# Lamp_Logic_Board_3.net
KiCad netlist of a schematic drawn in EAGLE
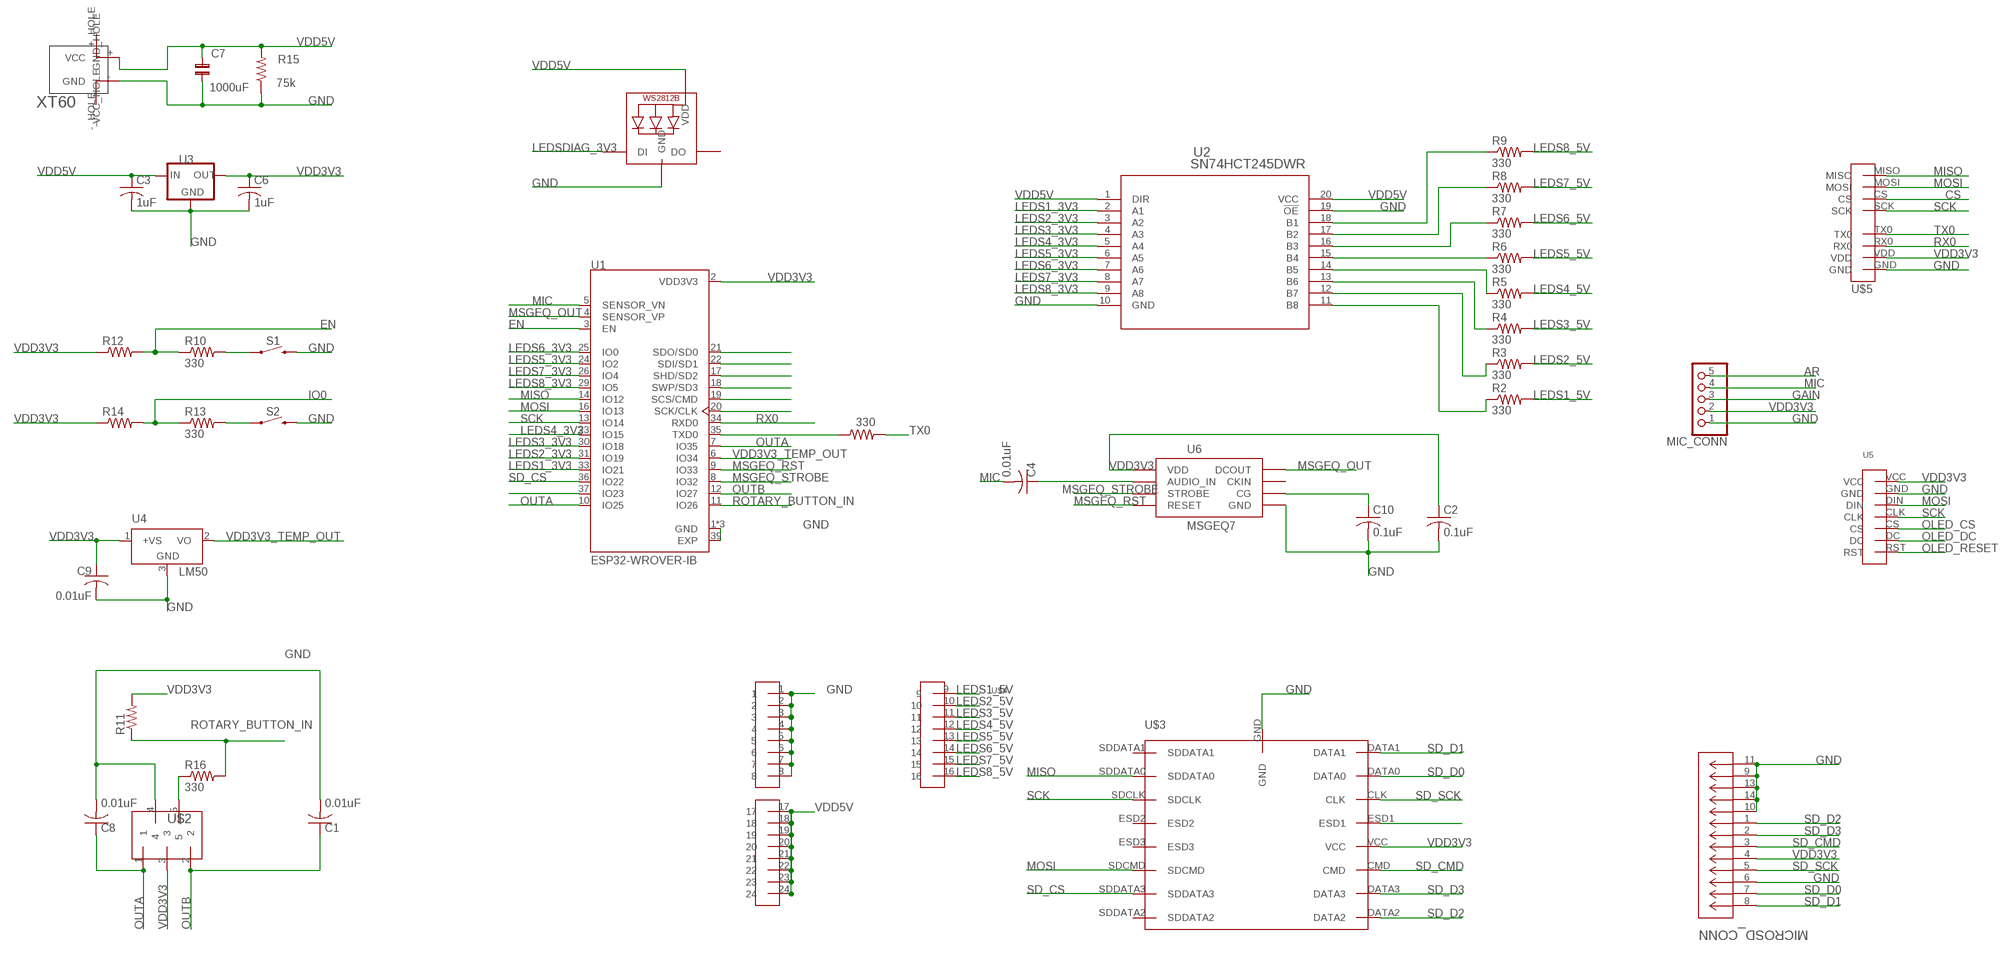
[diagram p0: schematic, sheet 1]

(export (version "E")
  (design (tool "Eeschema 10.0.6"))
  (components
    (comp (ref "C1")
      (value "0.01uF")
      (footprint "eagle-import:C0402")
      (libsource (lib "eagle-import") (part "C-USC0402"))
    )
    (comp (ref "C2")
      (value "0.1uF")
      (footprint "eagle-import:C0805")
      (libsource (lib "eagle-import") (part "C-USC0805"))
    )
    (comp (ref "C3")
      (value "1uF")
      (footprint "eagle-import:C0402")
      (libsource (lib "eagle-import") (part "C-USC0402"))
    )
    (comp (ref "C4")
      (value "0.01uF")
      (footprint "eagle-import:C0402")
      (libsource (lib "eagle-import") (part "C-USC0402"))
    )
    (comp (ref "C6")
      (value "1uF")
      (footprint "eagle-import:C0402")
      (libsource (lib "eagle-import") (part "C-USC0402"))
    )
    (comp (ref "C7")
      (value "1000uF")
      (footprint "eagle-import:ENP2,0-5")
      (libsource (lib "eagle-import") (part "C-BP-2,0X5"))
    )
    (comp (ref "C8")
      (value "0.01uF")
      (footprint "eagle-import:C0402")
      (libsource (lib "eagle-import") (part "C-USC0402"))
    )
    (comp (ref "C9")
      (value "0.01uF")
      (footprint "eagle-import:C0402")
      (libsource (lib "eagle-import") (part "C-USC0402"))
    )
    (comp (ref "C10")
      (value "0.1uF")
      (footprint "eagle-import:C0805")
      (libsource (lib "eagle-import") (part "C-USC0805"))
    )
    (comp (ref "LED1")
      (value "WS2812B5050")
      (footprint "eagle-import:WS2812B")
      (fields (field (name "MF") "Seeed Technology") (field (name "MP") "WS2812B"))
      (libsource (lib "eagle-import") (part "WS2812B5050"))
    )
    (comp (ref "MICROSD_CONN")
      (value "LLC")
      (footprint "eagle-import:CON00218_8")
      (libsource (lib "eagle-import") (part "LLC"))
    )
    (comp (ref "MIC_CONN")
      (value "PINHD-1X5")
      (footprint "eagle-import:1X05")
      (libsource (lib "eagle-import") (part "PINHD-1X5"))
    )
    (comp (ref "R1")
      (value "330")
      (footprint "eagle-import:R1206")
      (libsource (lib "eagle-import") (part "R-US_R1206"))
    )
    (comp (ref "R2")
      (value "330")
      (footprint "eagle-import:R1206")
      (libsource (lib "eagle-import") (part "R-US_R1206"))
    )
    (comp (ref "R3")
      (value "330")
      (footprint "eagle-import:R1206")
      (libsource (lib "eagle-import") (part "R-US_R1206"))
    )
    (comp (ref "R4")
      (value "330")
      (footprint "eagle-import:R1206")
      (libsource (lib "eagle-import") (part "R-US_R1206"))
    )
    (comp (ref "R5")
      (value "330")
      (footprint "eagle-import:R1206")
      (libsource (lib "eagle-import") (part "R-US_R1206"))
    )
    (comp (ref "R6")
      (value "330")
      (footprint "eagle-import:R1206")
      (libsource (lib "eagle-import") (part "R-US_R1206"))
    )
    (comp (ref "R7")
      (value "330")
      (footprint "eagle-import:R1206")
      (libsource (lib "eagle-import") (part "R-US_R1206"))
    )
    (comp (ref "R8")
      (value "330")
      (footprint "eagle-import:R1206")
      (libsource (lib "eagle-import") (part "R-US_R1206"))
    )
    (comp (ref "R9")
      (value "330")
      (footprint "eagle-import:R1206")
      (libsource (lib "eagle-import") (part "R-US_R1206"))
    )
    (comp (ref "R10")
      (value "330")
      (footprint "eagle-import:R1206")
      (libsource (lib "eagle-import") (part "R-US_R1206"))
    )
    (comp (ref "R11")
      (value "R-US_R0603")
      (footprint "eagle-import:R0603")
      (libsource (lib "eagle-import") (part "R-US_R0603"))
    )
    (comp (ref "R12")
      (value "R-US_R0603")
      (footprint "eagle-import:R0603")
      (libsource (lib "eagle-import") (part "R-US_R0603"))
    )
    (comp (ref "R13")
      (value "330")
      (footprint "eagle-import:R1206")
      (libsource (lib "eagle-import") (part "R-US_R1206"))
    )
    (comp (ref "R14")
      (value "R-US_R0603")
      (footprint "eagle-import:R0603")
      (libsource (lib "eagle-import") (part "R-US_R0603"))
    )
    (comp (ref "R15")
      (value "75k")
      (footprint "eagle-import:0309_12")
      (libsource (lib "eagle-import") (part "R-US_0309/12"))
    )
    (comp (ref "R16")
      (value "330")
      (footprint "eagle-import:R1206")
      (libsource (lib "eagle-import") (part "R-US_R1206"))
    )
    (comp (ref "S1")
      (value "MOMENTARY-SWITCH-SPST-SMD-6.0X3.5MM")
      (footprint "eagle-import:TACTILE_SWITCH_SMD_6.0X3.5MM")
      (libsource (lib "eagle-import") (part "MOMENTARY-SWITCH-SPST-SMD-6.0X3.5MM"))
    )
    (comp (ref "S2")
      (value "MOMENTARY-SWITCH-SPST-SMD-6.0X3.5MM")
      (footprint "eagle-import:TACTILE_SWITCH_SMD_6.0X3.5MM")
      (libsource (lib "eagle-import") (part "MOMENTARY-SWITCH-SPST-SMD-6.0X3.5MM"))
    )
    (comp (ref "U$1")
      (value "XT60")
      (footprint "eagle-import:XT60")
      (libsource (lib "eagle-import") (part "XT60"))
    )
    (comp (ref "U$2")
      (value "EN11-HSM1AF15")
      (footprint "eagle-import:EN11-HSM")
      (libsource (lib "eagle-import") (part "EN11-HSM1AF15"))
    )
    (comp (ref "U$3")
      (value "CM1624-08DE")
      (footprint "eagle-import:CM1624-08DE")
      (libsource (lib "eagle-import") (part "CM1624-08DE"))
    )
    (comp (ref "U$4")
      (value "3X8PINHEAD")
      (footprint "eagle-import:3X8PINHEAD")
      (libsource (lib "eagle-import") (part "3X8PINHEAD"))
    )
    (comp (ref "U$5")
      (value "2X4PINHEAD")
      (footprint "eagle-import:2X4PINHEAD")
      (libsource (lib "eagle-import") (part "2X4PINHEAD"))
    )
    (comp (ref "U1")
      (value "ESP32-WROVER-IB")
      (footprint "eagle-import:XCVR_ESP32-WROVER-I")
      (fields (field (name "MF") "Espressif Systems") (field (name "MP") "ESP32-WROVER-I"))
      (libsource (lib "eagle-import") (part "ESP32-WROVER-I"))
    )
    (comp (ref "U2")
      (value "SN74HCT245DWR")
      (footprint "eagle-import:DW20")
      (libsource (lib "eagle-import") (part "SN74HCT245DWR"))
    )
    (comp (ref "U3")
      (value "LM1117MP-1.8")
      (footprint "eagle-import:SOT223")
      (fields (field (name "MF") "Texas Instruments"))
      (libsource (lib "eagle-import") (part "LM1117?-MP1.8"))
    )
    (comp (ref "U4")
      (value "LM50")
      (footprint "eagle-import:SOT23")
      (libsource (lib "eagle-import") (part "LM50"))
    )
    (comp (ref "U5")
      (value "SPIOLED_STANDOFF")
      (footprint "eagle-import:SPIOLED_STADOFF")
      (libsource (lib "eagle-import") (part "SPIOLED_STANDOFF"))
    )
    (comp (ref "U6")
      (value "MSGEQ7DIL")
      (footprint "eagle-import:DIL-08")
      (fields
        (field (name "DIGI-KEY_PART_NUMBER") "1568-1544-ND")
        (field (name "MF") "SparkFun Electronics")
        (field (name "MP") "MSGEQ7")
      )
      (libsource (lib "eagle-import") (part "MSGEQ7DIL"))
    )
  )
  (nets
    (net (code "1") (name "/AR") (class "Default")
      (node (ref "MIC_CONN") (pin "5") (pinfunction "5_5") (pintype "passive"))
    )
    (net (code "2") (name "/CS") (class "Default")
      (node (ref "U$5") (pin "CS") (pinfunction "CS_CS") (pintype "bidirectional"))
    )
    (net (code "3") (name "/EN") (class "Default")
      (node (ref "R10") (pin "1") (pinfunction "1_1") (pintype "passive"))
      (node (ref "R12") (pin "2") (pinfunction "2_2") (pintype "passive"))
      (node (ref "U1") (pin "3") (pinfunction "EN_3") (pintype "input"))
    )
    (net (code "4") (name "/GAIN") (class "Default")
      (node (ref "MIC_CONN") (pin "3") (pinfunction "3_3") (pintype "passive"))
    )
    (net (code "5") (name "/GND") (class "Default")
      (node (ref "C1") (pin "2") (pinfunction "2_2") (pintype "passive"))
      (node (ref "C10") (pin "2") (pinfunction "2_2") (pintype "passive"))
      (node (ref "C2") (pin "2") (pinfunction "2_2") (pintype "passive"))
      (node (ref "C3") (pin "2") (pinfunction "2_2") (pintype "passive"))
      (node (ref "C6") (pin "2") (pinfunction "2_2") (pintype "passive"))
      (node (ref "C7") (pin "1") (pinfunction "1_1") (pintype "passive"))
      (node (ref "C8") (pin "2") (pinfunction "2_2") (pintype "passive"))
      (node (ref "C9") (pin "2") (pinfunction "2_2") (pintype "passive"))
      (node (ref "LED1") (pin "3-GND") (pinfunction "GND_3-GND") (pintype "power_in"))
      (node (ref "MICROSD_CONN") (pin "10") (pinfunction "10_10") (pintype "passive"))
      (node (ref "MICROSD_CONN") (pin "11") (pinfunction "11_11") (pintype "passive"))
      (node (ref "MICROSD_CONN") (pin "13") (pinfunction "13_13") (pintype "passive"))
      (node (ref "MICROSD_CONN") (pin "14") (pinfunction "14_14") (pintype "passive"))
      (node (ref "MICROSD_CONN") (pin "6") (pinfunction "6_6") (pintype "passive"))
      (node (ref "MICROSD_CONN") (pin "9") (pinfunction "9_9") (pintype "passive"))
      (node (ref "MIC_CONN") (pin "1") (pinfunction "1_1") (pintype "passive"))
      (node (ref "R15") (pin "1") (pinfunction "1_1") (pintype "passive"))
      (node (ref "S1") (pin "2") (pinfunction "2_2") (pintype "passive"))
      (node (ref "S2") (pin "2") (pinfunction "2_2") (pintype "passive"))
      (node (ref "U$1") (pin "-") (pinfunction "GND_-") (pintype "bidirectional"))
      (node (ref "U$2") (pin "4") (pinfunction "4_4") (pintype "bidirectional"))
      (node (ref "U$3") (pin "GND") (pinfunction "GND_GND") (pintype "bidirectional"))
      (node (ref "U$4") (pin "1") (pinfunction "1_1") (pintype "bidirectional"))
      (node (ref "U$4") (pin "2") (pinfunction "2_2") (pintype "bidirectional"))
      (node (ref "U$4") (pin "3") (pinfunction "3_3") (pintype "bidirectional"))
      (node (ref "U$4") (pin "4") (pinfunction "4_4") (pintype "bidirectional"))
      (node (ref "U$4") (pin "5") (pinfunction "5_5") (pintype "bidirectional"))
      (node (ref "U$4") (pin "6") (pinfunction "6_6") (pintype "bidirectional"))
      (node (ref "U$4") (pin "7") (pinfunction "7_7") (pintype "bidirectional"))
      (node (ref "U$4") (pin "8") (pinfunction "8_8") (pintype "bidirectional"))
      (node (ref "U$5") (pin "GND") (pinfunction "GND_GND") (pintype "bidirectional"))
      (node (ref "U1") (pin "1") (pinfunction "GND_1") (pintype "power_in"))
      (node (ref "U1") (pin "15") (pinfunction "GND_15") (pintype "power_in"))
      (node (ref "U1") (pin "38") (pinfunction "GND_38") (pintype "power_in"))
      (node (ref "U1") (pin "39") (pinfunction "EXP_39") (pintype "power_in"))
      (node (ref "U2") (pin "10") (pinfunction "GND_10") (pintype "power_in"))
      (node (ref "U2") (pin "19") (pinfunction "~{OE}_19") (pintype "input"))
      (node (ref "U3") (pin "1") (pinfunction "GND_1") (pintype "input"))
      (node (ref "U4") (pin "3") (pinfunction "GND_3") (pintype "power_in"))
      (node (ref "U5") (pin "GND") (pinfunction "GND_GND") (pintype "bidirectional"))
      (node (ref "U6") (pin "2") (pinfunction "GND_2") (pintype "bidirectional"))
    )
    (net (code "6") (name "/IO0") (class "Default")
      (node (ref "R13") (pin "1") (pinfunction "1_1") (pintype "passive"))
      (node (ref "R14") (pin "2") (pinfunction "2_2") (pintype "passive"))
    )
    (net (code "7") (name "/LEDS1_3V3") (class "Default")
      (node (ref "U1") (pin "33") (pinfunction "IO21_33") (pintype "bidirectional"))
      (node (ref "U2") (pin "2") (pinfunction "A1_2") (pintype "bidirectional"))
    )
    (net (code "8") (name "/LEDS1_5V") (class "Default")
      (node (ref "R2") (pin "2") (pinfunction "2_2") (pintype "passive"))
      (node (ref "U$4") (pin "9") (pinfunction "9_9") (pintype "bidirectional"))
    )
    (net (code "9") (name "/LEDS2_3V3") (class "Default")
      (node (ref "U1") (pin "31") (pinfunction "IO19_31") (pintype "bidirectional"))
      (node (ref "U2") (pin "3") (pinfunction "A2_3") (pintype "bidirectional"))
    )
    (net (code "10") (name "/LEDS2_5V") (class "Default")
      (node (ref "R3") (pin "2") (pinfunction "2_2") (pintype "passive"))
      (node (ref "U$4") (pin "10") (pinfunction "10_10") (pintype "bidirectional"))
    )
    (net (code "11") (name "/LEDS3_3V3") (class "Default")
      (node (ref "U1") (pin "30") (pinfunction "IO18_30") (pintype "bidirectional"))
      (node (ref "U2") (pin "4") (pinfunction "A3_4") (pintype "bidirectional"))
    )
    (net (code "12") (name "/LEDS3_5V") (class "Default")
      (node (ref "R4") (pin "2") (pinfunction "2_2") (pintype "passive"))
      (node (ref "U$4") (pin "11") (pinfunction "11_11") (pintype "bidirectional"))
    )
    (net (code "13") (name "/LEDS4_3V3") (class "Default")
      (node (ref "U1") (pin "23") (pinfunction "IO15_23") (pintype "bidirectional"))
      (node (ref "U2") (pin "5") (pinfunction "A4_5") (pintype "bidirectional"))
    )
    (net (code "14") (name "/LEDS4_5V") (class "Default")
      (node (ref "R5") (pin "2") (pinfunction "2_2") (pintype "passive"))
      (node (ref "U$4") (pin "12") (pinfunction "12_12") (pintype "bidirectional"))
    )
    (net (code "15") (name "/LEDS5_3V3") (class "Default")
      (node (ref "U1") (pin "24") (pinfunction "IO2_24") (pintype "bidirectional"))
      (node (ref "U2") (pin "6") (pinfunction "A5_6") (pintype "bidirectional"))
    )
    (net (code "16") (name "/LEDS5_5V") (class "Default")
      (node (ref "R6") (pin "2") (pinfunction "2_2") (pintype "passive"))
      (node (ref "U$4") (pin "13") (pinfunction "13_13") (pintype "bidirectional"))
    )
    (net (code "17") (name "/LEDS6_3V3") (class "Default")
      (node (ref "U1") (pin "25") (pinfunction "IO0_25") (pintype "bidirectional"))
      (node (ref "U2") (pin "7") (pinfunction "A6_7") (pintype "bidirectional"))
    )
    (net (code "18") (name "/LEDS6_5V") (class "Default")
      (node (ref "R7") (pin "2") (pinfunction "2_2") (pintype "passive"))
      (node (ref "U$4") (pin "14") (pinfunction "14_14") (pintype "bidirectional"))
    )
    (net (code "19") (name "/LEDS7_3V3") (class "Default")
      (node (ref "U1") (pin "26") (pinfunction "IO4_26") (pintype "bidirectional"))
      (node (ref "U2") (pin "8") (pinfunction "A7_8") (pintype "bidirectional"))
    )
    (net (code "20") (name "/LEDS7_5V") (class "Default")
      (node (ref "R8") (pin "2") (pinfunction "2_2") (pintype "passive"))
      (node (ref "U$4") (pin "15") (pinfunction "15_15") (pintype "bidirectional"))
    )
    (net (code "21") (name "/LEDS8_3V3") (class "Default")
      (node (ref "U1") (pin "29") (pinfunction "IO5_29") (pintype "bidirectional"))
      (node (ref "U2") (pin "9") (pinfunction "A8_9") (pintype "bidirectional"))
    )
    (net (code "22") (name "/LEDS8_5V") (class "Default")
      (node (ref "R9") (pin "2") (pinfunction "2_2") (pintype "passive"))
      (node (ref "U$4") (pin "16") (pinfunction "16_16") (pintype "bidirectional"))
    )
    (net (code "23") (name "/LEDSDIAG_3V3") (class "Default")
      (node (ref "LED1") (pin "4-DIN") (pinfunction "DI_4-DIN") (pintype "input"))
    )
    (net (code "24") (name "/MIC") (class "Default")
      (node (ref "C4") (pin "2") (pinfunction "2_2") (pintype "passive"))
      (node (ref "MIC_CONN") (pin "4") (pinfunction "4_4") (pintype "passive"))
      (node (ref "U1") (pin "5") (pinfunction "SENSOR_VN_5") (pintype "input"))
    )
    (net (code "25") (name "/MISO") (class "Default")
      (node (ref "U$3") (pin "SDDATA0") (pinfunction "SDDATA0_SDDATA0") (pintype "bidirectional"))
      (node (ref "U$5") (pin "MISO") (pinfunction "MISO_MISO") (pintype "bidirectional"))
      (node (ref "U1") (pin "14") (pinfunction "IO12_14") (pintype "bidirectional"))
    )
    (net (code "26") (name "/MOSI") (class "Default")
      (node (ref "U$3") (pin "SDCMD") (pinfunction "SDCMD_SDCMD") (pintype "bidirectional"))
      (node (ref "U$5") (pin "MOSI") (pinfunction "MOSI_MOSI") (pintype "bidirectional"))
      (node (ref "U1") (pin "16") (pinfunction "IO13_16") (pintype "bidirectional"))
      (node (ref "U5") (pin "DIN") (pinfunction "DIN_DIN") (pintype "bidirectional"))
    )
    (net (code "27") (name "/MSGEQ_OUT") (class "Default")
      (node (ref "U1") (pin "4") (pinfunction "SENSOR_VP_4") (pintype "input"))
      (node (ref "U6") (pin "3") (pinfunction "DCOUT_3") (pintype "bidirectional"))
    )
    (net (code "28") (name "/MSGEQ_RST") (class "Default")
      (node (ref "U1") (pin "9") (pinfunction "IO33_9") (pintype "bidirectional"))
      (node (ref "U6") (pin "7") (pinfunction "RESET_7") (pintype "input"))
    )
    (net (code "29") (name "/MSGEQ_STROBE") (class "Default")
      (node (ref "U1") (pin "8") (pinfunction "IO32_8") (pintype "bidirectional"))
      (node (ref "U6") (pin "4") (pinfunction "STROBE_4") (pintype "input"))
    )
    (net (code "30") (name "/OLED_CS") (class "Default")
      (node (ref "U5") (pin "CS") (pinfunction "CS_CS") (pintype "bidirectional"))
    )
    (net (code "31") (name "/OLED_DC") (class "Default")
      (node (ref "U5") (pin "DC") (pinfunction "DC_DC") (pintype "bidirectional"))
    )
    (net (code "32") (name "/OLED_RESET") (class "Default")
      (node (ref "U5") (pin "RST") (pinfunction "RST_RST") (pintype "bidirectional"))
    )
    (net (code "33") (name "/OUTA") (class "Default")
      (node (ref "C8") (pin "1") (pinfunction "1_1") (pintype "passive"))
      (node (ref "U$2") (pin "1") (pinfunction "1_1") (pintype "passive"))
      (node (ref "U1") (pin "10") (pinfunction "IO25_10") (pintype "bidirectional"))
      (node (ref "U1") (pin "7") (pinfunction "IO35_7") (pintype "input"))
    )
    (net (code "34") (name "/OUTB") (class "Default")
      (node (ref "C1") (pin "1") (pinfunction "1_1") (pintype "passive"))
      (node (ref "U$2") (pin "2") (pinfunction "2_2") (pintype "passive"))
      (node (ref "U1") (pin "12") (pinfunction "IO27_12") (pintype "bidirectional"))
    )
    (net (code "35") (name "/ROTARY_BUTTON_IN") (class "Default")
      (node (ref "R11") (pin "1") (pinfunction "1_1") (pintype "passive"))
      (node (ref "R16") (pin "2") (pinfunction "2_2") (pintype "passive"))
      (node (ref "U1") (pin "11") (pinfunction "IO26_11") (pintype "bidirectional"))
    )
    (net (code "36") (name "/RX0") (class "Default")
      (node (ref "U$5") (pin "RX0") (pinfunction "RX0_RX0") (pintype "bidirectional"))
      (node (ref "U1") (pin "34") (pinfunction "RXD0_34") (pintype "bidirectional"))
    )
    (net (code "37") (name "/SCK") (class "Default")
      (node (ref "U$3") (pin "SDCLK") (pinfunction "SDCLK_SDCLK") (pintype "bidirectional"))
      (node (ref "U$5") (pin "SCK") (pinfunction "SCK_SCK") (pintype "bidirectional"))
      (node (ref "U1") (pin "13") (pinfunction "IO14_13") (pintype "bidirectional"))
      (node (ref "U5") (pin "CLK") (pinfunction "CLK_CLK") (pintype "bidirectional"))
    )
    (net (code "38") (name "/SD_CMD") (class "Default")
      (node (ref "MICROSD_CONN") (pin "3") (pinfunction "3_3") (pintype "passive"))
      (node (ref "U$3") (pin "CMD") (pinfunction "CMD_CMD") (pintype "bidirectional"))
    )
    (net (code "39") (name "/SD_CS") (class "Default")
      (node (ref "U$3") (pin "SDDATA3") (pinfunction "SDDATA3_SDDATA3") (pintype "bidirectional"))
      (node (ref "U1") (pin "36") (pinfunction "IO22_36") (pintype "bidirectional"))
    )
    (net (code "40") (name "/SD_D0") (class "Default")
      (node (ref "MICROSD_CONN") (pin "7") (pinfunction "7_7") (pintype "passive"))
      (node (ref "U$3") (pin "DATA0") (pinfunction "DATA0_DATA0") (pintype "bidirectional"))
    )
    (net (code "41") (name "/SD_D1") (class "Default")
      (node (ref "MICROSD_CONN") (pin "8") (pinfunction "8_8") (pintype "passive"))
      (node (ref "U$3") (pin "DATA1") (pinfunction "DATA1_DATA1") (pintype "bidirectional"))
    )
    (net (code "42") (name "/SD_D2") (class "Default")
      (node (ref "MICROSD_CONN") (pin "1") (pinfunction "1_1") (pintype "passive"))
      (node (ref "U$3") (pin "DATA2") (pinfunction "DATA2_DATA2") (pintype "bidirectional"))
    )
    (net (code "43") (name "/SD_D3") (class "Default")
      (node (ref "MICROSD_CONN") (pin "2") (pinfunction "2_2") (pintype "passive"))
      (node (ref "U$3") (pin "DATA3") (pinfunction "DATA3_DATA3") (pintype "bidirectional"))
    )
    (net (code "44") (name "/SD_SCK") (class "Default")
      (node (ref "MICROSD_CONN") (pin "5") (pinfunction "5_5") (pintype "passive"))
      (node (ref "U$3") (pin "CLK") (pinfunction "CLK_CLK") (pintype "bidirectional"))
    )
    (net (code "45") (name "/TX0") (class "Default")
      (node (ref "R1") (pin "2") (pinfunction "2_2") (pintype "passive"))
      (node (ref "U$5") (pin "TX0") (pinfunction "TX0_TX0") (pintype "bidirectional"))
    )
    (net (code "46") (name "/VDD3V3") (class "Default")
      (node (ref "C2") (pin "1") (pinfunction "1_1") (pintype "passive"))
      (node (ref "C6") (pin "1") (pinfunction "1_1") (pintype "passive"))
      (node (ref "C9") (pin "1") (pinfunction "1_1") (pintype "passive"))
      (node (ref "MICROSD_CONN") (pin "4") (pinfunction "4_4") (pintype "passive"))
      (node (ref "MIC_CONN") (pin "2") (pinfunction "2_2") (pintype "passive"))
      (node (ref "R11") (pin "2") (pinfunction "2_2") (pintype "passive"))
      (node (ref "R12") (pin "1") (pinfunction "1_1") (pintype "passive"))
      (node (ref "R14") (pin "1") (pinfunction "1_1") (pintype "passive"))
      (node (ref "U$2") (pin "3") (pinfunction "3_3") (pintype "passive"))
      (node (ref "U$3") (pin "VCC") (pinfunction "VCC_VCC") (pintype "bidirectional"))
      (node (ref "U$5") (pin "VDD") (pinfunction "VDD_VDD") (pintype "bidirectional"))
      (node (ref "U1") (pin "2") (pinfunction "VDD3V3_2") (pintype "power_in"))
      (node (ref "U3") (pin "2") (pinfunction "OUT_2") (pintype "passive"))
      (node (ref "U3") (pin "4") (pinfunction "OUT_4") (pintype "passive"))
      (node (ref "U4") (pin "1") (pinfunction "+VS_1") (pintype "input"))
      (node (ref "U5") (pin "VCC") (pinfunction "VCC_VCC") (pintype "bidirectional"))
      (node (ref "U6") (pin "1") (pinfunction "VDD_1") (pintype "input"))
    )
    (net (code "47") (name "/VDD3V3_TEMP_OUT") (class "Default")
      (node (ref "U1") (pin "6") (pinfunction "IO34_6") (pintype "input"))
      (node (ref "U4") (pin "2") (pinfunction "VO_2") (pintype "input"))
    )
    (net (code "48") (name "/VDD5V") (class "Default")
      (node (ref "C3") (pin "1") (pinfunction "1_1") (pintype "passive"))
      (node (ref "C7") (pin "2") (pinfunction "2_2") (pintype "passive"))
      (node (ref "LED1") (pin "1-VDD") (pinfunction "VDD_1-VDD") (pintype "power_in"))
      (node (ref "R15") (pin "2") (pinfunction "2_2") (pintype "passive"))
      (node (ref "U$1") (pin "+") (pinfunction "VCC_+") (pintype "bidirectional"))
      (node (ref "U$4") (pin "17") (pinfunction "17_17") (pintype "bidirectional"))
      (node (ref "U$4") (pin "18") (pinfunction "18_18") (pintype "bidirectional"))
      (node (ref "U$4") (pin "19") (pinfunction "19_19") (pintype "bidirectional"))
      (node (ref "U$4") (pin "20") (pinfunction "20_20") (pintype "bidirectional"))
      (node (ref "U$4") (pin "21") (pinfunction "21_21") (pintype "bidirectional"))
      (node (ref "U$4") (pin "22") (pinfunction "22_22") (pintype "bidirectional"))
      (node (ref "U$4") (pin "23") (pinfunction "23_23") (pintype "bidirectional"))
      (node (ref "U$4") (pin "24") (pinfunction "24_24") (pintype "bidirectional"))
      (node (ref "U2") (pin "1") (pinfunction "DIR_1") (pintype "input"))
      (node (ref "U2") (pin "20") (pinfunction "VCC_20") (pintype "power_in"))
      (node (ref "U3") (pin "3") (pinfunction "IN_3") (pintype "input"))
    )
    (net (code "49") (name "Net-(R10-Pad2)") (class "Default")
      (node (ref "R10") (pin "2") (pinfunction "2_2") (pintype "passive"))
      (node (ref "S1") (pin "1") (pinfunction "1_1") (pintype "passive"))
    )
    (net (code "50") (name "Net-(R13-Pad2)") (class "Default")
      (node (ref "R13") (pin "2") (pinfunction "2_2") (pintype "passive"))
      (node (ref "S2") (pin "1") (pinfunction "1_1") (pintype "passive"))
    )
    (net (code "51") (name "Net-(R16-Pad1)") (class "Default")
      (node (ref "R16") (pin "1") (pinfunction "1_1") (pintype "passive"))
      (node (ref "U$2") (pin "5") (pinfunction "5_5") (pintype "bidirectional"))
    )
    (net (code "52") (name "Net-(U1-TXD0)") (class "Default")
      (node (ref "R1") (pin "1") (pinfunction "1_1") (pintype "passive"))
      (node (ref "U1") (pin "35") (pinfunction "TXD0_35") (pintype "bidirectional"))
    )
    (net (code "53") (name "Net-(U2-B1)") (class "Default")
      (node (ref "R9") (pin "1") (pinfunction "1_1") (pintype "passive"))
      (node (ref "U2") (pin "18") (pinfunction "B1_18") (pintype "bidirectional"))
    )
    (net (code "54") (name "Net-(U2-B2)") (class "Default")
      (node (ref "R8") (pin "1") (pinfunction "1_1") (pintype "passive"))
      (node (ref "U2") (pin "17") (pinfunction "B2_17") (pintype "bidirectional"))
    )
    (net (code "55") (name "Net-(U2-B3)") (class "Default")
      (node (ref "R7") (pin "1") (pinfunction "1_1") (pintype "passive"))
      (node (ref "U2") (pin "16") (pinfunction "B3_16") (pintype "bidirectional"))
    )
    (net (code "56") (name "Net-(U2-B4)") (class "Default")
      (node (ref "R6") (pin "1") (pinfunction "1_1") (pintype "passive"))
      (node (ref "U2") (pin "15") (pinfunction "B4_15") (pintype "bidirectional"))
    )
    (net (code "57") (name "Net-(U2-B5)") (class "Default")
      (node (ref "R5") (pin "1") (pinfunction "1_1") (pintype "passive"))
      (node (ref "U2") (pin "14") (pinfunction "B5_14") (pintype "bidirectional"))
    )
    (net (code "58") (name "Net-(U2-B6)") (class "Default")
      (node (ref "R4") (pin "1") (pinfunction "1_1") (pintype "passive"))
      (node (ref "U2") (pin "13") (pinfunction "B6_13") (pintype "bidirectional"))
    )
    (net (code "59") (name "Net-(U2-B7)") (class "Default")
      (node (ref "R3") (pin "1") (pinfunction "1_1") (pintype "passive"))
      (node (ref "U2") (pin "12") (pinfunction "B7_12") (pintype "bidirectional"))
    )
    (net (code "60") (name "Net-(U2-B8)") (class "Default")
      (node (ref "R2") (pin "1") (pinfunction "1_1") (pintype "passive"))
      (node (ref "U2") (pin "11") (pinfunction "B8_11") (pintype "bidirectional"))
    )
    (net (code "61") (name "Net-(U6-AUDIO_IN)") (class "Default")
      (node (ref "C4") (pin "1") (pinfunction "1_1") (pintype "passive"))
      (node (ref "U6") (pin "5") (pinfunction "AUDIO_IN_5") (pintype "input"))
    )
    (net (code "62") (name "Net-(U6-CG)") (class "Default")
      (node (ref "C10") (pin "1") (pinfunction "1_1") (pintype "passive"))
      (node (ref "U6") (pin "6") (pinfunction "CG_6") (pintype "bidirectional"))
    )
    (net (code "63") (name "unconnected-(LED1-DO-Pad2-DOUT)") (class "Default")
      (node (ref "LED1") (pin "2-DOUT") (pinfunction "DO_2-DOUT") (pintype "output"))
    )
    (net (code "64") (name "unconnected-(U$1-GND_HOLE-Pad-_HOLE)") (class "Default")
      (node (ref "U$1") (pin "-_HOLE") (pinfunction "GND_HOLE_-_HOLE") (pintype "bidirectional"))
    )
    (net (code "65") (name "unconnected-(U$1-VCC_HOLE-Pad+_HOLE)") (class "Default")
      (node (ref "U$1") (pin "+_HOLE") (pinfunction "VCC_HOLE_+_HOLE") (pintype "bidirectional"))
    )
    (net (code "66") (name "unconnected-(U$3-PadESD1)") (class "Default")
      (node (ref "U$3") (pin "ESD1") (pinfunction "ESD1_ESD1") (pintype "bidirectional"))
    )
    (net (code "67") (name "unconnected-(U$3-PadESD2)") (class "Default")
      (node (ref "U$3") (pin "ESD2") (pinfunction "ESD2_ESD2") (pintype "bidirectional"))
    )
    (net (code "68") (name "unconnected-(U$3-PadESD3)") (class "Default")
      (node (ref "U$3") (pin "ESD3") (pinfunction "ESD3_ESD3") (pintype "bidirectional"))
    )
    (net (code "69") (name "unconnected-(U$3-PadSDDATA1)") (class "Default")
      (node (ref "U$3") (pin "SDDATA1") (pinfunction "SDDATA1_SDDATA1") (pintype "bidirectional"))
    )
    (net (code "70") (name "unconnected-(U$3-PadSDDATA2)") (class "Default")
      (node (ref "U$3") (pin "SDDATA2") (pinfunction "SDDATA2_SDDATA2") (pintype "bidirectional"))
    )
    (net (code "71") (name "unconnected-(U1-IO23-Pad37)") (class "Default")
      (node (ref "U1") (pin "37") (pinfunction "IO23_37") (pintype "bidirectional"))
    )
    (net (code "72") (name "unconnected-(U1-SCK{slash}CLK-Pad20)") (class "Default")
      (node (ref "U1") (pin "20") (pinfunction "SCK/CLK_20") (pintype "bidirectional"))
    )
    (net (code "73") (name "unconnected-(U1-SCS{slash}CMD-Pad19)") (class "Default")
      (node (ref "U1") (pin "19") (pinfunction "SCS/CMD_19") (pintype "bidirectional"))
    )
    (net (code "74") (name "unconnected-(U1-SDI{slash}SD1-Pad22)") (class "Default")
      (node (ref "U1") (pin "22") (pinfunction "SDI/SD1_22") (pintype "bidirectional"))
    )
    (net (code "75") (name "unconnected-(U1-SDO{slash}SD0-Pad21)") (class "Default")
      (node (ref "U1") (pin "21") (pinfunction "SDO/SD0_21") (pintype "bidirectional"))
    )
    (net (code "76") (name "unconnected-(U1-SHD{slash}SD2-Pad17)") (class "Default")
      (node (ref "U1") (pin "17") (pinfunction "SHD/SD2_17") (pintype "bidirectional"))
    )
    (net (code "77") (name "unconnected-(U1-SWP{slash}SD3-Pad18)") (class "Default")
      (node (ref "U1") (pin "18") (pinfunction "SWP/SD3_18") (pintype "bidirectional"))
    )
    (net (code "78") (name "unconnected-(U6-CKIN-Pad8)") (class "Default")
      (node (ref "U6") (pin "8") (pinfunction "CKIN_8") (pintype "bidirectional"))
    )
  )
)
